# power.net
KiCad netlist of a schematic drawn in Altium Designer
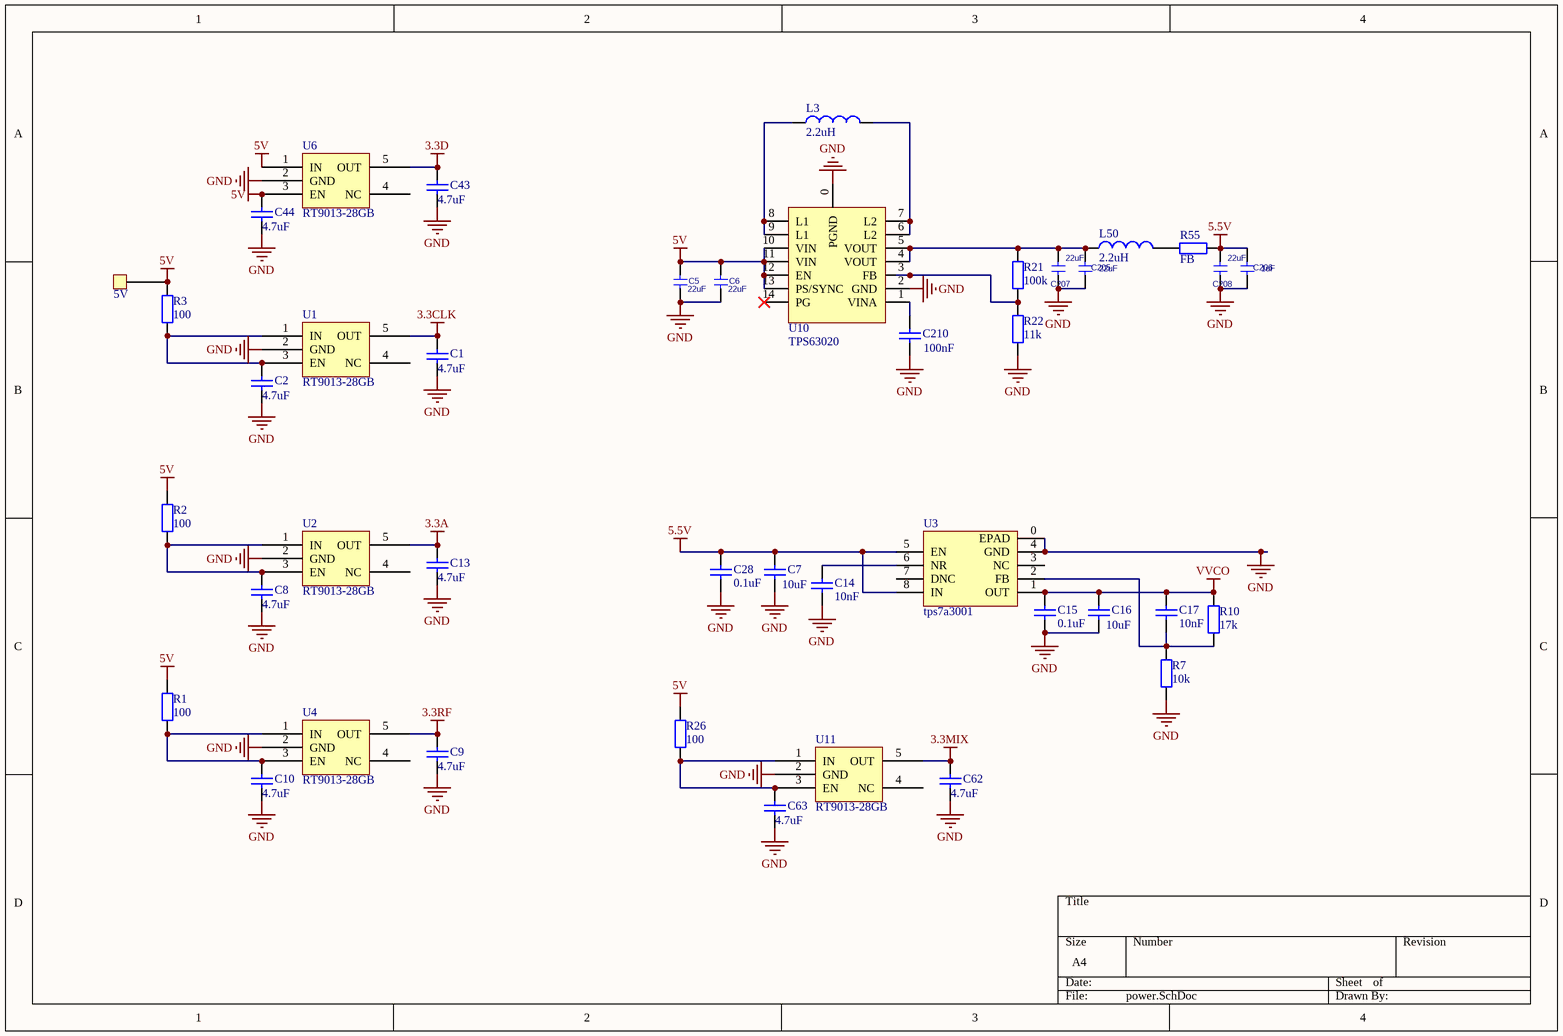
[diagram p0: power.SchDoc]

(export (version "E")
  (design (tool "Eeschema 10.0.6"))
  (components
    (comp (ref "5V") (value "TestPad") (footprint "TestPad") (libsource (lib "sch") (part "TestPad")))
    (comp (ref "C1")
      (value "4.7uF")
      (footprint "0603")
      (description "Capacitor")
      (fields (field (name "PUBLISHER") "Altium Limited"))
      (libsource (lib "RTC6705") (part "Cap"))
    )
    (comp (ref "C2")
      (value "4.7uF")
      (footprint "0603")
      (description "Capacitor")
      (fields (field (name "PUBLISHER") "Altium Limited"))
      (libsource (lib "RTC6705") (part "Cap"))
    )
    (comp (ref "C5") (value "22uF") (footprint "0805") (libsource (lib "*") (part "C")))
    (comp (ref "C6") (value "22uF") (footprint "0805") (libsource (lib "*") (part "C")))
    (comp (ref "C7")
      (value "10uF")
      (footprint "0805")
      (description "Capacitor")
      (fields (field (name "PUBLISHER") "Altium Limited"))
      (libsource (lib "RTC6705") (part "Cap"))
    )
    (comp (ref "C8")
      (value "4.7uF")
      (footprint "0603")
      (description "Capacitor")
      (fields (field (name "PUBLISHER") "Altium Limited"))
      (libsource (lib "RTC6705") (part "Cap"))
    )
    (comp (ref "C9")
      (value "4.7uF")
      (footprint "0603")
      (description "Capacitor")
      (fields (field (name "PUBLISHER") "Altium Limited"))
      (libsource (lib "RTC6705") (part "Cap"))
    )
    (comp (ref "C10")
      (value "4.7uF")
      (footprint "0603")
      (description "Capacitor")
      (fields (field (name "PUBLISHER") "Altium Limited"))
      (libsource (lib "RTC6705") (part "Cap"))
    )
    (comp (ref "C13")
      (value "4.7uF")
      (footprint "0603")
      (description "Capacitor")
      (fields (field (name "PUBLISHER") "Altium Limited"))
      (libsource (lib "RTC6705") (part "Cap"))
    )
    (comp (ref "C14")
      (value "10nF")
      (footprint "0402")
      (description "Capacitor")
      (fields (field (name "PUBLISHER") "Altium Limited"))
      (libsource (lib "RTC6705") (part "Cap"))
    )
    (comp (ref "C15")
      (value "0.1uF")
      (footprint "0603L")
      (description "Capacitor")
      (fields (field (name "PUBLISHER") "Altium Limited"))
      (libsource (lib "RTC6705") (part "Cap"))
    )
    (comp (ref "C16")
      (value "10uF")
      (footprint "0805")
      (description "Capacitor")
      (fields (field (name "PUBLISHER") "Altium Limited"))
      (libsource (lib "RTC6705") (part "Cap"))
    )
    (comp (ref "C17")
      (value "10nF")
      (footprint "0402")
      (description "Capacitor")
      (fields (field (name "PUBLISHER") "Altium Limited"))
      (libsource (lib "RTC6705") (part "Cap"))
    )
    (comp (ref "C28")
      (value "0.1uF")
      (footprint "0603L")
      (description "Capacitor")
      (fields (field (name "PUBLISHER") "Altium Limited"))
      (libsource (lib "RTC6705") (part "Cap"))
    )
    (comp (ref "C43")
      (value "4.7uF")
      (footprint "0603")
      (description "Capacitor")
      (fields (field (name "PUBLISHER") "Altium Limited"))
      (libsource (lib "RTC6705") (part "Cap"))
    )
    (comp (ref "C44")
      (value "4.7uF")
      (footprint "0603")
      (description "Capacitor")
      (fields (field (name "PUBLISHER") "Altium Limited"))
      (libsource (lib "RTC6705") (part "Cap"))
    )
    (comp (ref "C62")
      (value "4.7uF")
      (footprint "0603")
      (description "Capacitor")
      (fields (field (name "PUBLISHER") "Altium Limited"))
      (libsource (lib "RTC6705") (part "Cap"))
    )
    (comp (ref "C63")
      (value "4.7uF")
      (footprint "0603")
      (description "Capacitor")
      (fields (field (name "PUBLISHER") "Altium Limited"))
      (libsource (lib "RTC6705") (part "Cap"))
    )
    (comp (ref "C205") (value "22uF") (footprint "0805") (libsource (lib "*") (part "C")))
    (comp (ref "C206") (value "1uF") (footprint "0805") (libsource (lib "*") (part "C")))
    (comp (ref "C207") (value "22uF") (footprint "0805") (libsource (lib "*") (part "C")))
    (comp (ref "C208") (value "22uF") (footprint "0805") (libsource (lib "*") (part "C")))
    (comp (ref "C210")
      (value "100nF")
      (footprint "0402")
      (description "Capacitor")
      (fields (field (name "PUBLISHER") "Altium Limited"))
      (libsource (lib "RTC6705") (part "Cap"))
    )
    (comp (ref "L3")
      (value "2.2uH")
      (footprint "L4015")
      (description "Inductor")
      (fields (field (name "PUBLISHER") "Altium Limited"))
      (libsource (lib "Miscellaneous Devices") (part "Inductor"))
    )
    (comp (ref "L50")
      (value "2.2uH")
      (footprint "L4015")
      (description "Inductor")
      (fields (field (name "PUBLISHER") "Altium Limited"))
      (libsource (lib "Miscellaneous Devices") (part "Inductor"))
    )
    (comp (ref "R1")
      (value "100")
      (footprint "0603")
      (description "Resistor")
      (fields (field (name "PUBLISHER") "Altium Limited"))
      (libsource (lib "Miscellaneous Devices") (part "Res2"))
    )
    (comp (ref "R2")
      (value "100")
      (footprint "0603")
      (description "Resistor")
      (fields (field (name "PUBLISHER") "Altium Limited"))
      (libsource (lib "Miscellaneous Devices") (part "Res2"))
    )
    (comp (ref "R3")
      (value "100")
      (footprint "0603")
      (description "Resistor")
      (fields (field (name "PUBLISHER") "Altium Limited"))
      (libsource (lib "Miscellaneous Devices") (part "Res2"))
    )
    (comp (ref "R7")
      (value "10k")
      (footprint "0402")
      (description "Resistor")
      (fields (field (name "PUBLISHER") "Altium Limited"))
      (libsource (lib "RTC6705") (part "Res2"))
    )
    (comp (ref "R10")
      (value "17k")
      (footprint "0402")
      (description "Resistor")
      (fields (field (name "PUBLISHER") "Altium Limited"))
      (libsource (lib "RTC6705") (part "Res2"))
    )
    (comp (ref "R21")
      (value "100k")
      (footprint "0402")
      (description "Resistor")
      (fields (field (name "PUBLISHER") "Altium Limited"))
      (libsource (lib "") (part "Res2_1"))
    )
    (comp (ref "R22")
      (value "11k")
      (footprint "0402")
      (description "Resistor")
      (fields (field (name "PUBLISHER") "Altium Limited"))
      (libsource (lib "") (part "Res2_1"))
    )
    (comp (ref "R26")
      (value "100")
      (footprint "0603")
      (description "Resistor")
      (fields (field (name "PUBLISHER") "Altium Limited"))
      (libsource (lib "Miscellaneous Devices") (part "Res2"))
    )
    (comp (ref "R55")
      (value "FB")
      (footprint "0603L")
      (description "Resistor")
      (fields (field (name "PUBLISHER") "Altium Limited"))
      (libsource (lib "") (part "Res2_1"))
    )
    (comp (ref "U1") (value "RT9013-28GB") (footprint "SOT23-5") (libsource (lib "RTC6705") (part "LP5907")))
    (comp (ref "U2") (value "RT9013-28GB") (footprint "SOT23-5") (libsource (lib "RTC6705") (part "LP5907")))
    (comp (ref "U3")
      (value "tps7a3001")
      (footprint "MSOP8/VSSOP8+PAD")
      (libsource (lib "F4SDR") (part "tps7a3001"))
    )
    (comp (ref "U4") (value "RT9013-28GB") (footprint "SOT23-5") (libsource (lib "RTC6705") (part "LP5907")))
    (comp (ref "U6") (value "RT9013-28GB") (footprint "SOT23-5") (libsource (lib "RTC6705") (part "LP5907")))
    (comp (ref "U10") (value "TPS63020") (footprint "TPS63020") (libsource (lib "sch") (part "TPS63020")))
    (comp (ref "U11") (value "RT9013-28GB") (footprint "SOT23-5") (libsource (lib "RTC6705") (part "LP5907")))
  )
  (nets
    (net (code "1") (name "3.3A") (class "Default")
      (node (ref "C13") (pin "2") (pinfunction "2_2") (pintype "passive"))
      (node (ref "U2") (pin "5") (pinfunction "OUT_5") (pintype "passive"))
    )
    (net (code "2") (name "3.3CLK") (class "Default")
      (node (ref "C1") (pin "2") (pinfunction "2_2") (pintype "passive"))
      (node (ref "U1") (pin "5") (pinfunction "OUT_5") (pintype "passive"))
    )
    (net (code "3") (name "3.3D") (class "Default")
      (node (ref "C43") (pin "2") (pinfunction "2_2") (pintype "passive"))
      (node (ref "U6") (pin "5") (pinfunction "OUT_5") (pintype "passive"))
    )
    (net (code "4") (name "3.3MIX") (class "Default")
      (node (ref "C62") (pin "2") (pinfunction "2_2") (pintype "passive"))
      (node (ref "U11") (pin "5") (pinfunction "OUT_5") (pintype "passive"))
    )
    (net (code "5") (name "3.3RF") (class "Default")
      (node (ref "C9") (pin "2") (pinfunction "2_2") (pintype "passive"))
      (node (ref "U4") (pin "5") (pinfunction "OUT_5") (pintype "passive"))
    )
    (net (code "6") (name "5.5V") (class "Default")
      (node (ref "C206") (pin "1") (pinfunction "1_1") (pintype "passive"))
      (node (ref "C208") (pin "1") (pinfunction "1_1") (pintype "passive"))
      (node (ref "C28") (pin "1") (pinfunction "1_1") (pintype "passive"))
      (node (ref "C7") (pin "2") (pinfunction "2_2") (pintype "passive"))
      (node (ref "R55") (pin "1") (pinfunction "1_1") (pintype "passive"))
      (node (ref "U3") (pin "5") (pinfunction "EN_5") (pintype "passive"))
      (node (ref "U3") (pin "8") (pinfunction "IN_8") (pintype "passive"))
    )
    (net (code "7") (name "5V") (class "Default")
      (node (ref "5V") (pin "1") (pinfunction "3_1") (pintype "passive"))
      (node (ref "C44") (pin "2") (pinfunction "2_2") (pintype "passive"))
      (node (ref "C5") (pin "1") (pinfunction "1_1") (pintype "passive"))
      (node (ref "C6") (pin "1") (pinfunction "1_1") (pintype "passive"))
      (node (ref "R1") (pin "2") (pinfunction "2_2") (pintype "passive"))
      (node (ref "R2") (pin "2") (pinfunction "2_2") (pintype "passive"))
      (node (ref "R26") (pin "2") (pinfunction "2_2") (pintype "passive"))
      (node (ref "R3") (pin "2") (pinfunction "2_2") (pintype "passive"))
      (node (ref "U10") (pin "10") (pinfunction "VIN_10") (pintype "passive"))
      (node (ref "U10") (pin "11") (pinfunction "VIN_11") (pintype "passive"))
      (node (ref "U10") (pin "12") (pinfunction "EN_12") (pintype "passive"))
      (node (ref "U10") (pin "13") (pinfunction "PS/SYNC_13") (pintype "passive"))
      (node (ref "U6") (pin "1") (pinfunction "IN_1") (pintype "passive"))
      (node (ref "U6") (pin "3") (pinfunction "EN_3") (pintype "passive"))
    )
    (net (code "8") (name "GND") (class "Default")
      (node (ref "C1") (pin "1") (pinfunction "1_1") (pintype "passive"))
      (node (ref "C10") (pin "1") (pinfunction "1_1") (pintype "passive"))
      (node (ref "C13") (pin "1") (pinfunction "1_1") (pintype "passive"))
      (node (ref "C14") (pin "2") (pinfunction "2_2") (pintype "passive"))
      (node (ref "C15") (pin "2") (pinfunction "2_2") (pintype "passive"))
      (node (ref "C16") (pin "1") (pinfunction "1_1") (pintype "passive"))
      (node (ref "C2") (pin "1") (pinfunction "1_1") (pintype "passive"))
      (node (ref "C205") (pin "2") (pinfunction "2_2") (pintype "passive"))
      (node (ref "C206") (pin "2") (pinfunction "2_2") (pintype "passive"))
      (node (ref "C207") (pin "2") (pinfunction "2_2") (pintype "passive"))
      (node (ref "C208") (pin "2") (pinfunction "2_2") (pintype "passive"))
      (node (ref "C210") (pin "2") (pinfunction "2_2") (pintype "passive"))
      (node (ref "C28") (pin "2") (pinfunction "2_2") (pintype "passive"))
      (node (ref "C43") (pin "1") (pinfunction "1_1") (pintype "passive"))
      (node (ref "C44") (pin "1") (pinfunction "1_1") (pintype "passive"))
      (node (ref "C5") (pin "2") (pinfunction "2_2") (pintype "passive"))
      (node (ref "C6") (pin "2") (pinfunction "2_2") (pintype "passive"))
      (node (ref "C62") (pin "1") (pinfunction "1_1") (pintype "passive"))
      (node (ref "C63") (pin "1") (pinfunction "1_1") (pintype "passive"))
      (node (ref "C7") (pin "1") (pinfunction "1_1") (pintype "passive"))
      (node (ref "C8") (pin "1") (pinfunction "1_1") (pintype "passive"))
      (node (ref "C9") (pin "1") (pinfunction "1_1") (pintype "passive"))
      (node (ref "R22") (pin "2") (pinfunction "2_2") (pintype "passive"))
      (node (ref "R7") (pin "1") (pinfunction "1_1") (pintype "passive"))
      (node (ref "U1") (pin "2") (pinfunction "GND_2") (pintype "passive"))
      (node (ref "U10") (pin "0") (pinfunction "PGND_0") (pintype "passive"))
      (node (ref "U10") (pin "2") (pinfunction "GND_2") (pintype "passive"))
      (node (ref "U11") (pin "2") (pinfunction "GND_2") (pintype "passive"))
      (node (ref "U2") (pin "2") (pinfunction "GND_2") (pintype "passive"))
      (node (ref "U3") (pin "0") (pinfunction "EPAD_0") (pintype "passive"))
      (node (ref "U3") (pin "4") (pinfunction "GND_4") (pintype "passive"))
      (node (ref "U4") (pin "2") (pinfunction "GND_2") (pintype "passive"))
      (node (ref "U6") (pin "2") (pinfunction "GND_2") (pintype "passive"))
    )
    (net (code "9") (name "Net-(C205-Pad1)") (class "Default")
      (node (ref "C205") (pin "1") (pinfunction "1_1") (pintype "passive"))
      (node (ref "C207") (pin "1") (pinfunction "1_1") (pintype "passive"))
      (node (ref "L50") (pin "1") (pinfunction "1_1") (pintype "passive"))
      (node (ref "R21") (pin "1") (pinfunction "1_1") (pintype "passive"))
      (node (ref "U10") (pin "4") (pinfunction "VOUT_4") (pintype "passive"))
      (node (ref "U10") (pin "5") (pinfunction "VOUT_5") (pintype "passive"))
    )
    (net (code "10") (name "Net-(L3-Pad1)") (class "Default")
      (node (ref "L3") (pin "1") (pinfunction "1_1") (pintype "passive"))
      (node (ref "U10") (pin "8") (pinfunction "L1_8") (pintype "passive"))
      (node (ref "U10") (pin "9") (pinfunction "L1_9") (pintype "passive"))
    )
    (net (code "11") (name "Net-(L3-Pad2)") (class "Default")
      (node (ref "L3") (pin "2") (pinfunction "2_2") (pintype "passive"))
      (node (ref "U10") (pin "6") (pinfunction "L2_6") (pintype "passive"))
      (node (ref "U10") (pin "7") (pinfunction "L2_7") (pintype "passive"))
    )
    (net (code "12") (name "Net-(L50-Pad2)") (class "Default")
      (node (ref "L50") (pin "2") (pinfunction "2_2") (pintype "passive"))
      (node (ref "R55") (pin "2") (pinfunction "2_2") (pintype "passive"))
    )
    (net (code "13") (name "Net-(U1-EN)") (class "Default")
      (node (ref "C2") (pin "2") (pinfunction "2_2") (pintype "passive"))
      (node (ref "R3") (pin "1") (pinfunction "1_1") (pintype "passive"))
      (node (ref "U1") (pin "1") (pinfunction "IN_1") (pintype "passive"))
      (node (ref "U1") (pin "3") (pinfunction "EN_3") (pintype "passive"))
    )
    (net (code "14") (name "Net-(U2-EN)") (class "Default")
      (node (ref "C8") (pin "2") (pinfunction "2_2") (pintype "passive"))
      (node (ref "R2") (pin "1") (pinfunction "1_1") (pintype "passive"))
      (node (ref "U2") (pin "1") (pinfunction "IN_1") (pintype "passive"))
      (node (ref "U2") (pin "3") (pinfunction "EN_3") (pintype "passive"))
    )
    (net (code "15") (name "Net-(U3-FB)") (class "Default")
      (node (ref "C17") (pin "2") (pinfunction "2_2") (pintype "passive"))
      (node (ref "R10") (pin "1") (pinfunction "1_1") (pintype "passive"))
      (node (ref "R7") (pin "2") (pinfunction "2_2") (pintype "passive"))
      (node (ref "U3") (pin "2") (pinfunction "FB_2") (pintype "passive"))
    )
    (net (code "16") (name "Net-(U3-NR)") (class "Default")
      (node (ref "C14") (pin "1") (pinfunction "1_1") (pintype "passive"))
      (node (ref "U3") (pin "6") (pinfunction "NR_6") (pintype "passive"))
    )
    (net (code "17") (name "Net-(U4-EN)") (class "Default")
      (node (ref "C10") (pin "2") (pinfunction "2_2") (pintype "passive"))
      (node (ref "R1") (pin "1") (pinfunction "1_1") (pintype "passive"))
      (node (ref "U4") (pin "1") (pinfunction "IN_1") (pintype "passive"))
      (node (ref "U4") (pin "3") (pinfunction "EN_3") (pintype "passive"))
    )
    (net (code "18") (name "Net-(U10-FB)") (class "Default")
      (node (ref "R21") (pin "2") (pinfunction "2_2") (pintype "passive"))
      (node (ref "R22") (pin "1") (pinfunction "1_1") (pintype "passive"))
      (node (ref "U10") (pin "3") (pinfunction "FB_3") (pintype "passive"))
    )
    (net (code "19") (name "Net-(U10-VINA)") (class "Default")
      (node (ref "C210") (pin "1") (pinfunction "1_1") (pintype "passive"))
      (node (ref "U10") (pin "1") (pinfunction "VINA_1") (pintype "passive"))
    )
    (net (code "20") (name "Net-(U11-EN)") (class "Default")
      (node (ref "C63") (pin "2") (pinfunction "2_2") (pintype "passive"))
      (node (ref "R26") (pin "1") (pinfunction "1_1") (pintype "passive"))
      (node (ref "U11") (pin "1") (pinfunction "IN_1") (pintype "passive"))
      (node (ref "U11") (pin "3") (pinfunction "EN_3") (pintype "passive"))
    )
    (net (code "21") (name "VVCO") (class "Default")
      (node (ref "C15") (pin "1") (pinfunction "1_1") (pintype "passive"))
      (node (ref "C16") (pin "2") (pinfunction "2_2") (pintype "passive"))
      (node (ref "C17") (pin "1") (pinfunction "1_1") (pintype "passive"))
      (node (ref "R10") (pin "2") (pinfunction "2_2") (pintype "passive"))
      (node (ref "U3") (pin "1") (pinfunction "OUT_1") (pintype "passive"))
    )
    (net (code "22") (name "unconnected-(U1-NC-Pad4)") (class "Default")
      (node (ref "U1") (pin "4") (pinfunction "NC_4") (pintype "passive"))
    )
    (net (code "23") (name "unconnected-(U2-NC-Pad4)") (class "Default")
      (node (ref "U2") (pin "4") (pinfunction "NC_4") (pintype "passive"))
    )
    (net (code "24") (name "unconnected-(U3-DNC-Pad7)") (class "Default")
      (node (ref "U3") (pin "7") (pinfunction "DNC_7") (pintype "passive"))
    )
    (net (code "25") (name "unconnected-(U3-NC-Pad3)") (class "Default")
      (node (ref "U3") (pin "3") (pinfunction "NC_3") (pintype "passive"))
    )
    (net (code "26") (name "unconnected-(U4-NC-Pad4)") (class "Default")
      (node (ref "U4") (pin "4") (pinfunction "NC_4") (pintype "passive"))
    )
    (net (code "27") (name "unconnected-(U6-NC-Pad4)") (class "Default")
      (node (ref "U6") (pin "4") (pinfunction "NC_4") (pintype "passive"))
    )
    (net (code "28") (name "unconnected-(U10-PG-Pad14)") (class "Default")
      (node (ref "U10") (pin "14") (pinfunction "PG_14") (pintype "passive+no_connect"))
    )
    (net (code "29") (name "unconnected-(U11-NC-Pad4)") (class "Default")
      (node (ref "U11") (pin "4") (pinfunction "NC_4") (pintype "passive"))
    )
  )
)
